# can.net
KiCad netlist of a schematic drawn in Altium Designer
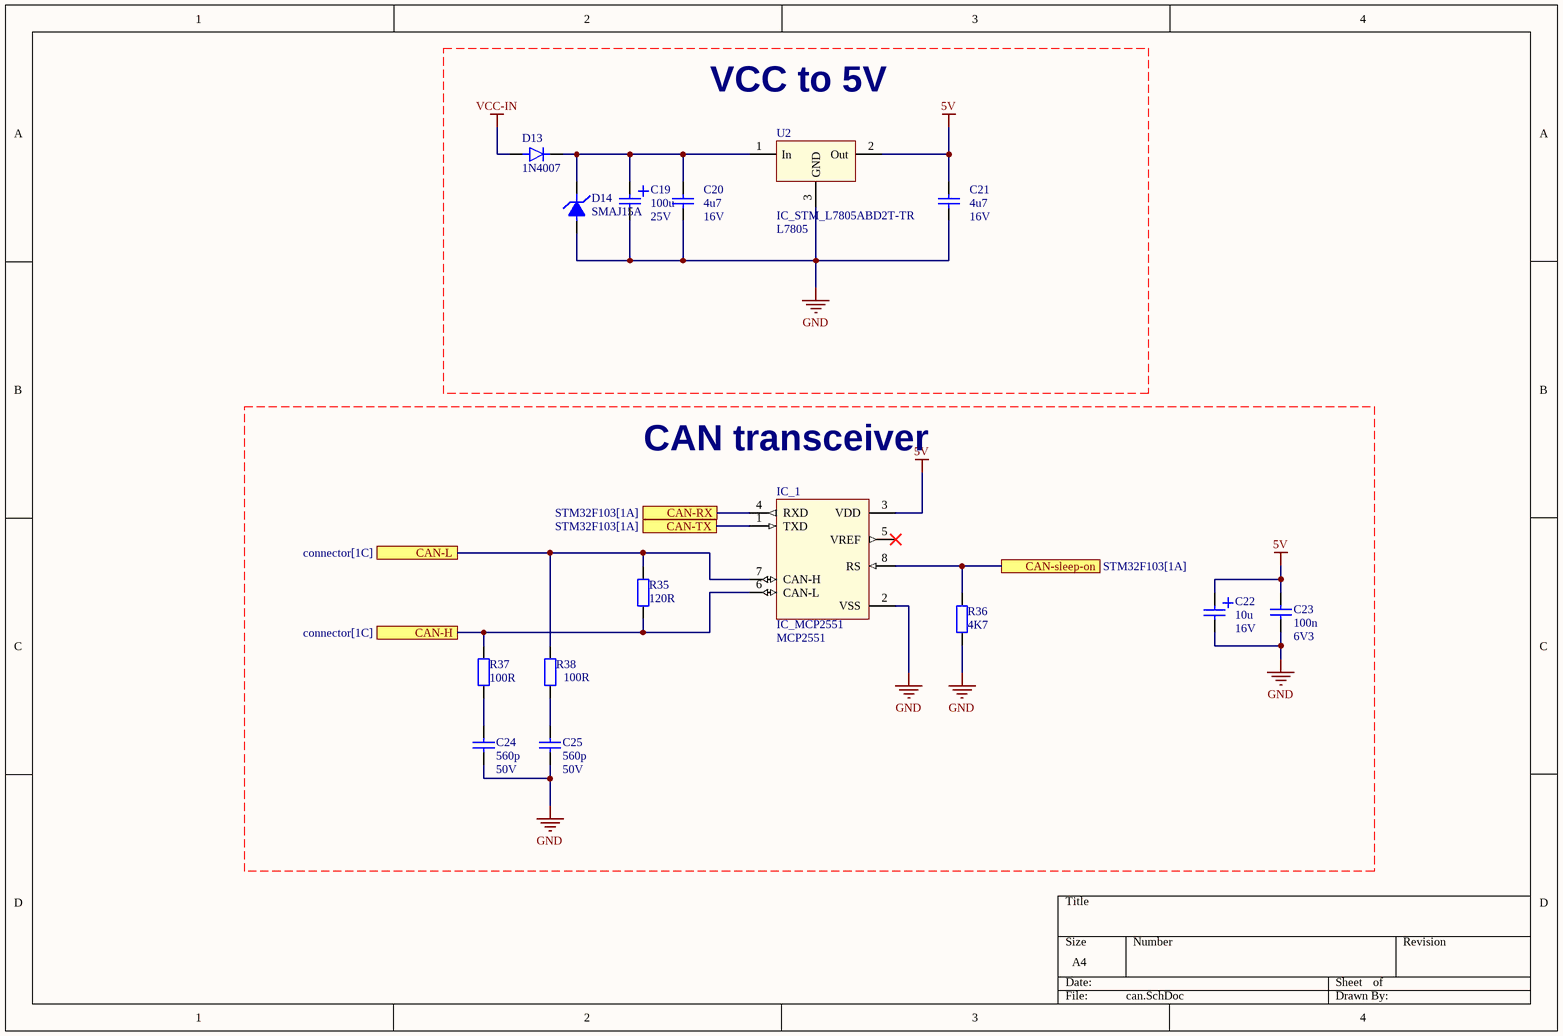
[diagram p0: can.SchDoc]

(export (version "E")
  (design (tool "Eeschema 10.0.6"))
  (components
    (comp (ref "C19")
      (value "CAP_POL")
      (footprint "CAPAE9983X102N")
      (description "PANASONIC - EEEFC1E101AP - CAP, ALU ELEC, 100UF, 25V, SMD, REEL")
      (fields
        (field (name "VALUE1") "100u")
        (field (name "VALUE2") "25V")
        (field (name "MANUFACTURER") "Panasonic")
      )
      (libsource (lib "DSW_Lib") (part "CAP_POL"))
    )
    (comp (ref "C20")
      (value "CAP")
      (footprint "CAPC2012X140N")
      (description "X7R 10% 0805")
      (fields
        (field (name "VALUE1") "4u7")
        (field (name "VALUE2") "16V")
        (field (name "MANUFACTURER") "MURATA")
      )
      (libsource (lib "DSW_Lib") (part "CAP"))
    )
    (comp (ref "C21")
      (value "CAP")
      (footprint "CAPC2012X140N")
      (description "X7R 10% 0805")
      (fields
        (field (name "VALUE1") "4u7")
        (field (name "VALUE2") "16V")
        (field (name "MANUFACTURER") "MURATA")
      )
      (libsource (lib "DSW_Lib") (part "CAP"))
    )
    (comp (ref "C22")
      (value "CAP_POL")
      (footprint "CAPAE430X550N")
      (description "ELCO 20%")
      (fields
        (field (name "VALUE1") "10u")
        (field (name "VALUE2") "16V")
        (field (name "MANUFACTURER") "Nichicon")
      )
      (libsource (lib "DSW_Lib") (part "CAP_POL"))
    )
    (comp (ref "C23")
      (value "CAP")
      (footprint "CAPC2012X88N")
      (description "X7R 10% 0805")
      (fields
        (field (name "VALUE1") "100n")
        (field (name "VALUE2") "6V3")
        (field (name "MANUFACTURER") "KEMET")
      )
      (libsource (lib "DSW_Lib") (part "CAP"))
    )
    (comp (ref "C24")
      (value "CAP")
      (footprint "CAPC2012X88N")
      (description "YAGEO (PHYCOMP) - CC0805JRNPO9BN561 - CAP, MLCC, C0G/NP0, 560PF, 50V, 0805")
      (fields
        (field (name "VALUE1") "560p")
        (field (name "VALUE2") "50V")
        (field (name "MANUFACTURER") "YAGEO")
      )
      (libsource (lib "DSW_Lib") (part "CAP"))
    )
    (comp (ref "C25")
      (value "CAP")
      (footprint "CAPC2012X88N")
      (description "YAGEO (PHYCOMP) - CC0805JRNPO9BN561 - CAP, MLCC, C0G/NP0, 560PF, 50V, 0805")
      (fields
        (field (name "VALUE1") "560p")
        (field (name "VALUE2") "50V")
        (field (name "MANUFACTURER") "YAGEO")
      )
      (libsource (lib "DSW_Lib") (part "CAP"))
    )
    (comp (ref "D13")
      (value "DIO")
      (footprint "DO-214AC")
      (description "M7 Diode, max 30A")
      (fields (field (name "VALUE1") "1N4007"))
      (libsource (lib "DSW_Lib") (part "DIO"))
    )
    (comp (ref "D14")
      (value "DIO_UNIDIRECTIONAL_TVS")
      (footprint "DO-214AC")
      (description "Transient Voltage Suppressors")
      (fields (field (name "VALUE1") "SMAJ15A") (field (name "MANUFACTURER") "Littelfuse"))
      (libsource (lib "DSW_Lib") (part "DIO_UNIDIRECTIONAL_TVS"))
    )
    (comp (ref "IC_1")
      (value "IC_MCP2551")
      (footprint "SOIC-8N")
      (description "High-speed CAN transceiver")
      (fields (field (name "VALUE1") "MCP2551") (field (name "MANUFACTURER") "Microchip"))
      (libsource (lib "DSW_Lib") (part "IC_MCP2551"))
    )
    (comp (ref "R35")
      (value "RES")
      (footprint "RESC2012X60N")
      (description "RESISTOR, 0805, 120R, 1%, SMD")
      (fields (field (name "VALUE1") "120R") (field (name "MANUFACTURER") "Yageo"))
      (libsource (lib "DSW_Lib") (part "RES"))
    )
    (comp (ref "R36")
      (value "RES")
      (footprint "RESC2012X60N")
      (description "RESISTOR, 0805, 4K7, 1%, SMD")
      (fields (field (name "VALUE1") "4K7") (field (name "MANUFACTURER") "Yageo"))
      (libsource (lib "DSW_Lib") (part "RES"))
    )
    (comp (ref "R37")
      (value "RES")
      (footprint "RESC2012X60N")
      (description "RESISTOR, 0805, 100R, 1%, SMD")
      (fields (field (name "VALUE1") "100R") (field (name "MANUFACTURER") "Yageo"))
      (libsource (lib "DSW_Lib") (part "RES"))
    )
    (comp (ref "R38")
      (value "RES")
      (footprint "RESC2012X60N")
      (description "RESISTOR, 0805, 100R, 1%, SMD")
      (fields (field (name "VALUE1") "100R") (field (name "MANUFACTURER") "Yageo"))
      (libsource (lib "DSW_Lib") (part "RES"))
    )
    (comp (ref "U2")
      (value "IC_STM_L7805ABD2T-TR")
      (footprint "IC_STM_L7805ABD2T-TR")
      (description "Linear Voltage Regulators 5.0V 1.0A Positive")
      (fields (field (name "VALUE1") "L7805") (field (name "MANUFACTURER") "STM"))
      (libsource (lib "DSW_Lib") (part "IC_STM_L7805ABD2T-TR"))
    )
  )
  (nets
    (net (code "1") (name "/CAN-H") (class "Default")
      (node (ref "IC_1") (pin "6") (pinfunction "CAN-L_6") (pintype "bidirectional"))
      (node (ref "R35") (pin "1") (pinfunction "1_1") (pintype "passive"))
      (node (ref "R37") (pin "2") (pinfunction "2_2") (pintype "passive"))
    )
    (net (code "2") (name "/CAN-L") (class "Default")
      (node (ref "IC_1") (pin "7") (pinfunction "CAN-H_7") (pintype "bidirectional"))
      (node (ref "R35") (pin "2") (pinfunction "2_2") (pintype "passive"))
      (node (ref "R38") (pin "2") (pinfunction "2_2") (pintype "passive"))
    )
    (net (code "3") (name "/CAN-RX") (class "Default")
      (node (ref "IC_1") (pin "4") (pinfunction "RXD_4") (pintype "output"))
    )
    (net (code "4") (name "/CAN-TX") (class "Default")
      (node (ref "IC_1") (pin "1") (pinfunction "TXD_1") (pintype "input"))
    )
    (net (code "5") (name "/CAN-sleep-on") (class "Default")
      (node (ref "IC_1") (pin "8") (pinfunction "RS_8") (pintype "input"))
      (node (ref "R36") (pin "2") (pinfunction "2_2") (pintype "passive"))
    )
    (net (code "6") (name "5V") (class "Default")
      (node (ref "C21") (pin "1") (pinfunction "1_1") (pintype "passive"))
      (node (ref "C22") (pin "1") (pinfunction "1_1") (pintype "passive"))
      (node (ref "C23") (pin "2") (pinfunction "2_2") (pintype "passive"))
      (node (ref "IC_1") (pin "3") (pinfunction "VDD_3") (pintype "power_in"))
      (node (ref "U2") (pin "2") (pinfunction "Out_2") (pintype "passive"))
    )
    (net (code "7") (name "GND") (class "Default")
      (node (ref "C19") (pin "2") (pinfunction "2_2") (pintype "passive"))
      (node (ref "C20") (pin "2") (pinfunction "2_2") (pintype "passive"))
      (node (ref "C21") (pin "2") (pinfunction "2_2") (pintype "passive"))
      (node (ref "C22") (pin "2") (pinfunction "2_2") (pintype "passive"))
      (node (ref "C23") (pin "1") (pinfunction "1_1") (pintype "passive"))
      (node (ref "C24") (pin "1") (pinfunction "1_1") (pintype "passive"))
      (node (ref "C25") (pin "1") (pinfunction "1_1") (pintype "passive"))
      (node (ref "D14") (pin "1") (pinfunction "1_1") (pintype "passive"))
      (node (ref "IC_1") (pin "2") (pinfunction "VSS_2") (pintype "power_in"))
      (node (ref "R36") (pin "1") (pinfunction "1_1") (pintype "passive"))
      (node (ref "U2") (pin "3") (pinfunction "GND_3") (pintype "passive"))
    )
    (net (code "8") (name "Net-(C24-Pad2)") (class "Default")
      (node (ref "C24") (pin "2") (pinfunction "2_2") (pintype "passive"))
      (node (ref "R37") (pin "1") (pinfunction "1_1") (pintype "passive"))
    )
    (net (code "9") (name "Net-(C25-Pad2)") (class "Default")
      (node (ref "C25") (pin "2") (pinfunction "2_2") (pintype "passive"))
      (node (ref "R38") (pin "1") (pinfunction "1_1") (pintype "passive"))
    )
    (net (code "10") (name "Net-(D13-K)") (class "Default")
      (node (ref "C19") (pin "1") (pinfunction "1_1") (pintype "passive"))
      (node (ref "C20") (pin "1") (pinfunction "1_1") (pintype "passive"))
      (node (ref "D13") (pin "2") (pinfunction "K_2") (pintype "passive"))
      (node (ref "D14") (pin "2") (pinfunction "2_2") (pintype "passive"))
      (node (ref "U2") (pin "1") (pinfunction "In_1") (pintype "passive"))
    )
    (net (code "11") (name "VCC-IN") (class "Default")
      (node (ref "D13") (pin "1") (pinfunction "A_1") (pintype "passive"))
    )
    (net (code "12") (name "unconnected-(IC_1-VREF-Pad5)") (class "Default")
      (node (ref "IC_1") (pin "5") (pinfunction "VREF_5") (pintype "output+no_connect"))
    )
  )
)
